# Spektrum_Adapter.net
KiCad netlist of a schematic drawn in Altium Designer
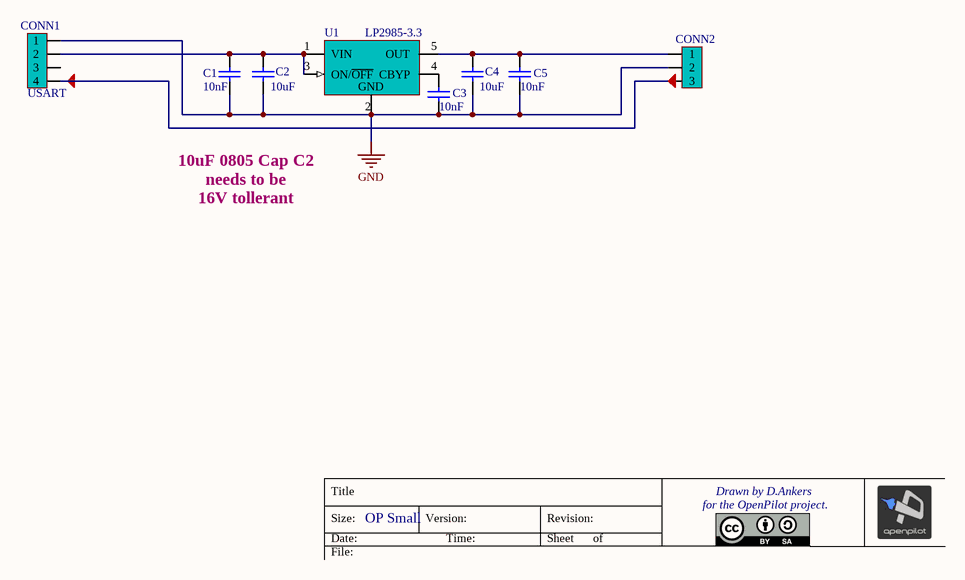
[diagram p0: Spektrum Adapter.SchDoc]

(export (version "E")
  (design (tool "Eeschema 10.0.6"))
  (components
    (comp (ref "C1")
      (value "10nF")
      (footprint "CAP603L")
      (description "Capacitor SMD")
      (fields (field (name "Comment") "Cap603") (field (name "PUBLISHER") "The OpenPilot Project"))
      (libsource (lib "OpenPilot") (part "Cap603"))
    )
    (comp (ref "C2")
      (value "10uF")
      (footprint "CAP805L")
      (description "Capacitor SMD")
      (fields (field (name "Comment") "Cap805") (field (name "PUBLISHER") "The OpenPilot Project"))
      (libsource (lib "OpenPilot") (part "Cap805"))
    )
    (comp (ref "C3")
      (value "10nF")
      (footprint "CAP603L")
      (description "Capacitor SMD")
      (fields (field (name "Comment") "Cap603") (field (name "PUBLISHER") "The OpenPilot Project"))
      (libsource (lib "OpenPilot") (part "Cap603"))
    )
    (comp (ref "C4")
      (value "10uF")
      (footprint "CAP805L")
      (description "Capacitor SMD")
      (fields (field (name "Comment") "Cap805") (field (name "PUBLISHER") "The OpenPilot Project"))
      (libsource (lib "OpenPilot") (part "Cap805"))
    )
    (comp (ref "C5")
      (value "10nF")
      (footprint "CAP603L")
      (description "Capacitor SMD")
      (fields (field (name "Comment") "Cap603") (field (name "PUBLISHER") "The OpenPilot Project"))
      (libsource (lib "OpenPilot") (part "Cap603"))
    )
    (comp (ref "CONN1")
      (value "USART")
      (footprint "JST SH 4 Pin Side Entry")
      (description "JST-SH 4-pin Side Entry Socket")
      (fields (field (name "MANUFACTURER") "Generic Components"))
      (libsource (lib "OpenPilot") (part "JST-SH 4-pin Side Entry Socket"))
    )
    (comp (ref "CONN2")
      (value "JST ZH 3 Pin")
      (footprint "JST ZH 3 PIN SIDE ENTRY")
      (description "JST ZH 1.5mm 3-pin Side Entry Socket")
      (fields
        (field (name "MANUFACTURER") "Generic Components")
        (field (name "PUBLISHER") "The OpenPilot Project")
      )
      (libsource (lib "OpenPilot") (part "JST ZH 3-pin Side Entry Socket"))
    )
    (comp (ref "U1")
      (value "LP2985-3.3")
      (footprint "SOT23-5L")
      (description "3.3V 150mA LDO Regulator")
      (libsource (lib "OpenPilot") (part "LP2985-3.3"))
    )
  )
  (nets
    (net (code "1") (name "GND") (class "Default")
      (node (ref "C1") (pin "2") (pinfunction "2_2") (pintype "passive"))
      (node (ref "C2") (pin "2") (pinfunction "2_2") (pintype "passive"))
      (node (ref "C3") (pin "2") (pinfunction "2_2") (pintype "passive"))
      (node (ref "C4") (pin "2") (pinfunction "2_2") (pintype "passive"))
      (node (ref "C5") (pin "2") (pinfunction "2_2") (pintype "passive"))
      (node (ref "CONN1") (pin "1") (pinfunction "1_1") (pintype "passive"))
      (node (ref "CONN2") (pin "2") (pinfunction "2_2") (pintype "power_in"))
      (node (ref "U1") (pin "2") (pinfunction "GND_2") (pintype "power_in"))
    )
    (net (code "2") (name "Net-(CONN1-Pad4)") (class "Default")
      (node (ref "CONN1") (pin "4") (pinfunction "4_4") (pintype "passive"))
      (node (ref "CONN2") (pin "3") (pinfunction "3_3") (pintype "passive"))
    )
    (net (code "3") (name "Net-(U1-CBYP)") (class "Default")
      (node (ref "C3") (pin "1") (pinfunction "1_1") (pintype "passive"))
      (node (ref "U1") (pin "4") (pinfunction "CBYP_4") (pintype "passive"))
    )
    (net (code "4") (name "Net-(U1-ON{slash}~{OFF})") (class "Default")
      (node (ref "C1") (pin "1") (pinfunction "1_1") (pintype "passive"))
      (node (ref "C2") (pin "1") (pinfunction "1_1") (pintype "passive"))
      (node (ref "CONN1") (pin "2") (pinfunction "2_2") (pintype "passive"))
      (node (ref "U1") (pin "1") (pinfunction "VIN_1") (pintype "power_in"))
      (node (ref "U1") (pin "3") (pinfunction "ON/~{OFF}_3") (pintype "input"))
    )
    (net (code "5") (name "Net-(U1-OUT)") (class "Default")
      (node (ref "C4") (pin "1") (pinfunction "1_1") (pintype "passive"))
      (node (ref "C5") (pin "1") (pinfunction "1_1") (pintype "passive"))
      (node (ref "CONN2") (pin "1") (pinfunction "1_1") (pintype "power_in"))
      (node (ref "U1") (pin "5") (pinfunction "OUT_5") (pintype "power_in"))
    )
    (net (code "6") (name "unconnected-(CONN1-Pad3)") (class "Default")
      (node (ref "CONN1") (pin "3") (pinfunction "3_3") (pintype "passive"))
    )
  )
)
